# design.net
KiCad netlist of a schematic drawn in Altium Designer
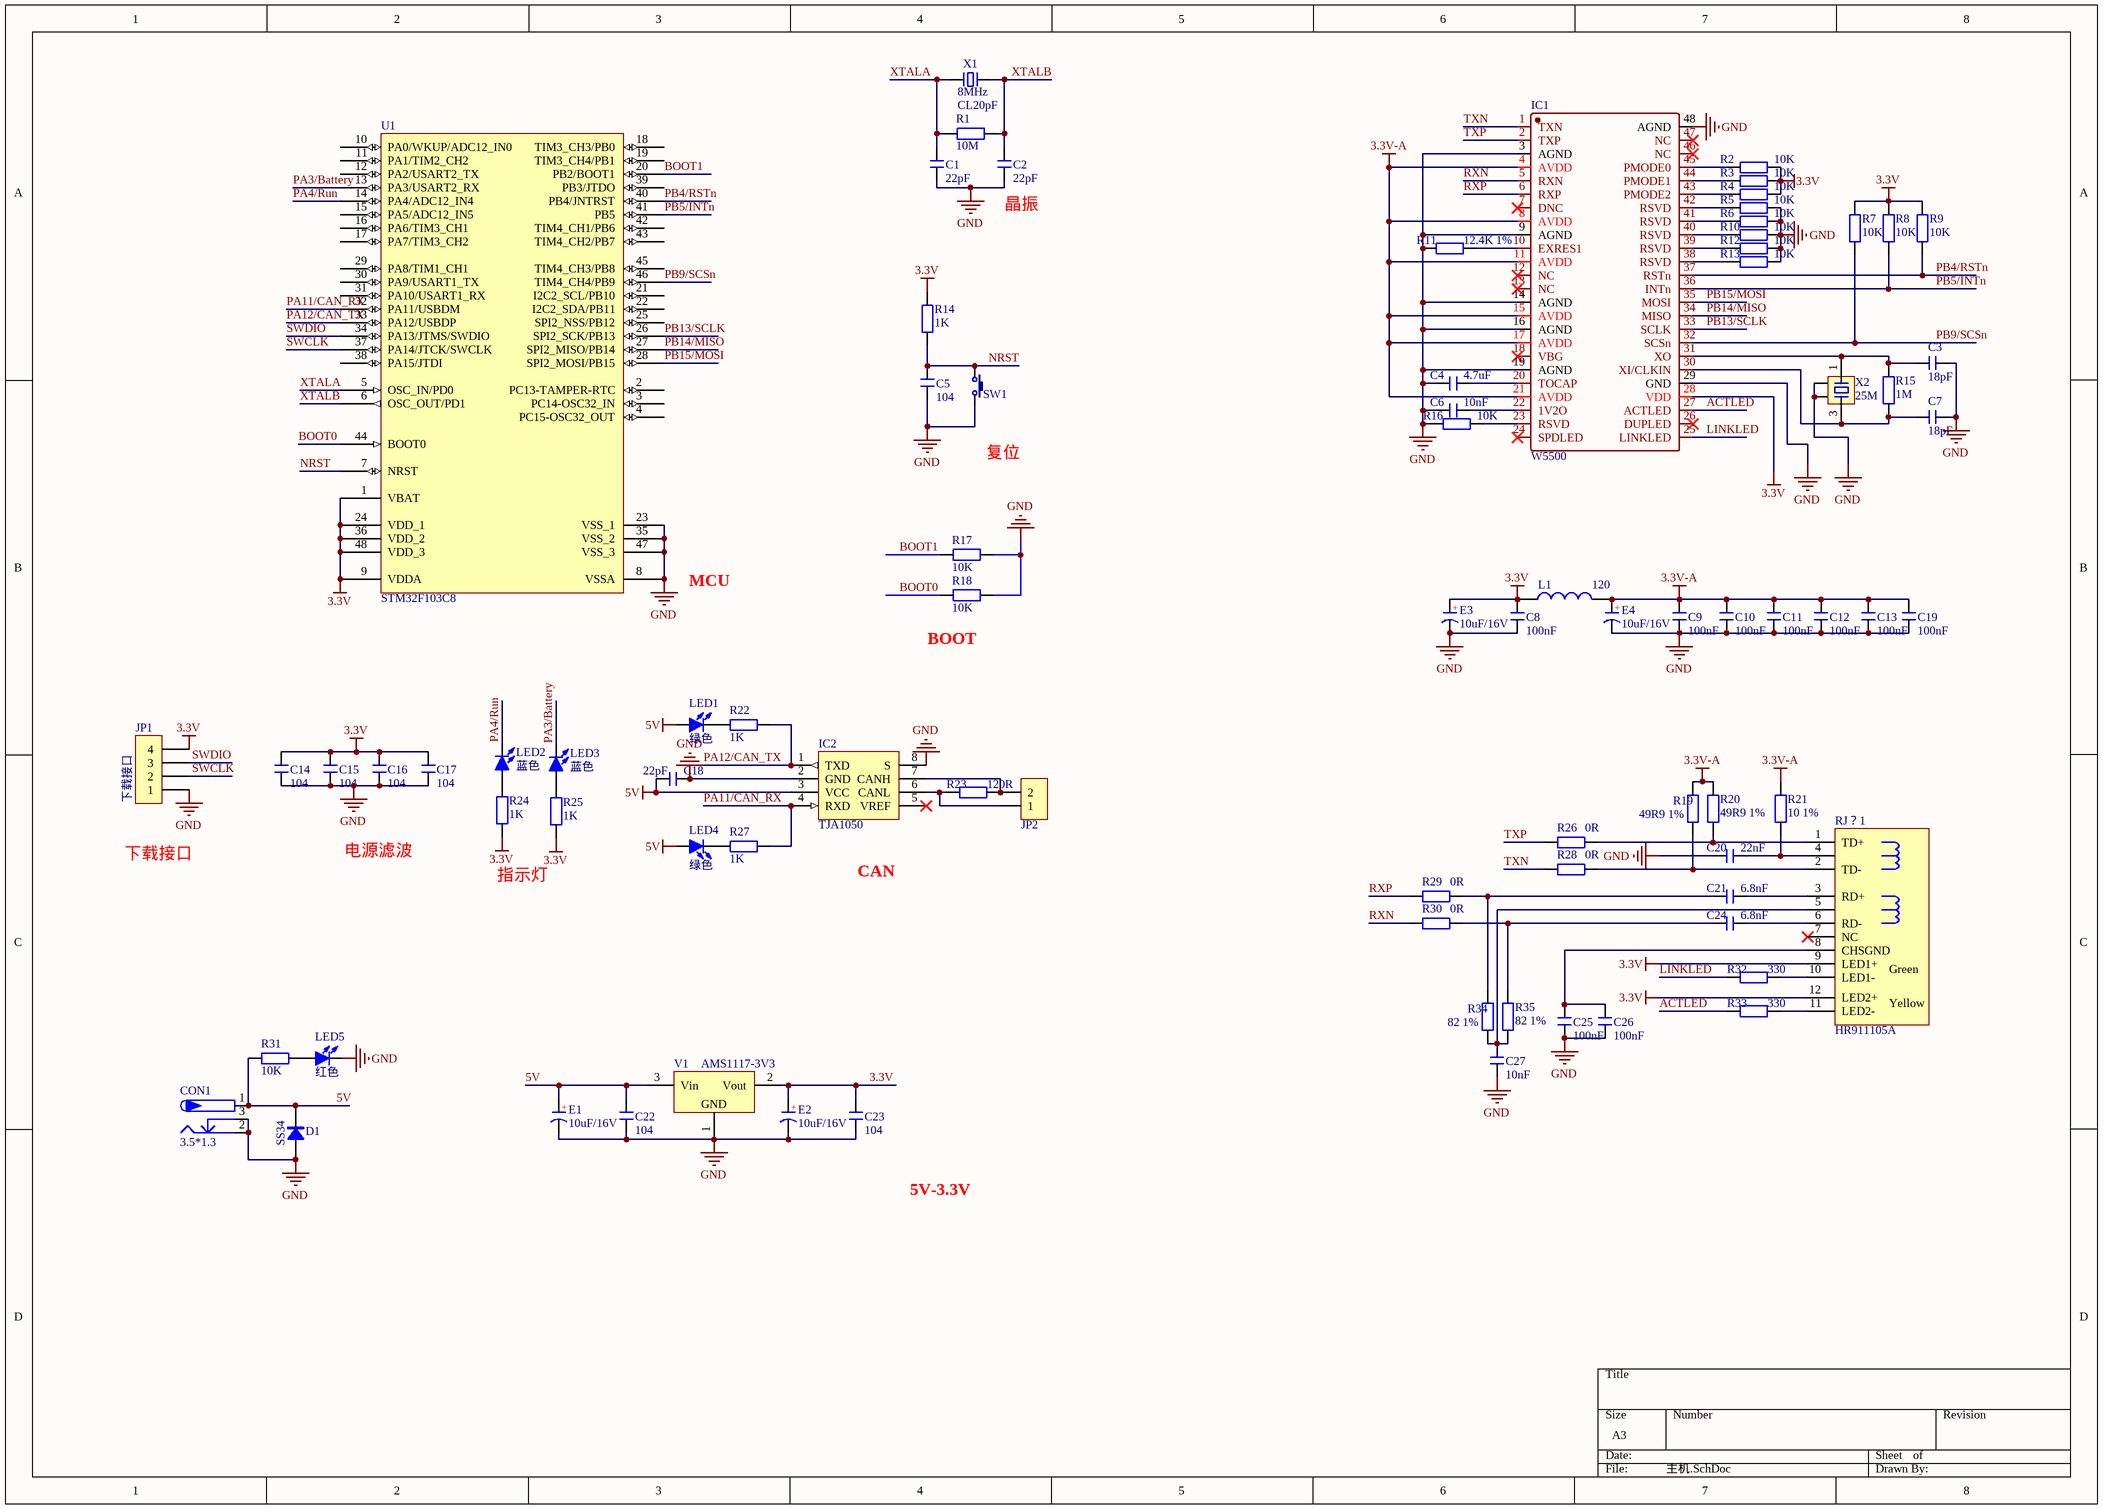
[diagram p0: 主机.SchDoc]

(export (version "E")
  (design (tool "Eeschema 10.0.6"))
  (components
    (comp (ref "C1")
      (value "22pF")
      (footprint "C 0402_L")
      (description "贴片电容")
      (libsource (lib "0.1 - 电阻-电容-电感") (part "C"))
    )
    (comp (ref "C2")
      (value "22pF")
      (footprint "C 0402_L")
      (description "贴片电容")
      (libsource (lib "0.1 - 电阻-电容-电感") (part "C"))
    )
    (comp (ref "C3")
      (value "18pF")
      (footprint "C 0402_L")
      (description "贴片电容")
      (libsource (lib "0.1 - 电阻-电容-电感") (part "C"))
    )
    (comp (ref "C4")
      (value "4.7uF")
      (footprint "C 0402_L")
      (description "贴片电容")
      (libsource (lib "0.1 - 电阻-电容-电感") (part "C"))
    )
    (comp (ref "C5")
      (value "104")
      (footprint "C 0603_L")
      (description "贴片电容")
      (libsource (lib "0.1 - 电阻-电容-电感") (part "C"))
    )
    (comp (ref "C6")
      (value "10nF")
      (footprint "C 0402_L")
      (description "贴片电容")
      (libsource (lib "0.1 - 电阻-电容-电感") (part "C"))
    )
    (comp (ref "C7")
      (value "18pF")
      (footprint "C 0402_L")
      (description "贴片电容")
      (libsource (lib "0.1 - 电阻-电容-电感") (part "C"))
    )
    (comp (ref "C8")
      (value "100nF")
      (footprint "C 0402_L")
      (description "贴片电容")
      (libsource (lib "0.1 - 电阻-电容-电感") (part "C"))
    )
    (comp (ref "C9")
      (value "100nF")
      (footprint "C 0402_L")
      (description "贴片电容")
      (libsource (lib "0.1 - 电阻-电容-电感") (part "C"))
    )
    (comp (ref "C10")
      (value "100nF")
      (footprint "C 0402_L")
      (description "贴片电容")
      (libsource (lib "0.1 - 电阻-电容-电感") (part "C"))
    )
    (comp (ref "C11")
      (value "100nF")
      (footprint "C 0402_L")
      (description "贴片电容")
      (libsource (lib "0.1 - 电阻-电容-电感") (part "C"))
    )
    (comp (ref "C12")
      (value "100nF")
      (footprint "C 0402_L")
      (description "贴片电容")
      (libsource (lib "0.1 - 电阻-电容-电感") (part "C"))
    )
    (comp (ref "C13")
      (value "100nF")
      (footprint "C 0402_L")
      (description "贴片电容")
      (libsource (lib "0.1 - 电阻-电容-电感") (part "C"))
    )
    (comp (ref "C14")
      (value "104")
      (footprint "C 0402_L")
      (description "贴片电容")
      (libsource (lib "0.1 - 电阻-电容-电感") (part "C"))
    )
    (comp (ref "C15")
      (value "104")
      (footprint "C 0402_L")
      (description "贴片电容")
      (libsource (lib "0.1 - 电阻-电容-电感") (part "C"))
    )
    (comp (ref "C16")
      (value "104")
      (footprint "C 0402_L")
      (description "贴片电容")
      (libsource (lib "0.1 - 电阻-电容-电感") (part "C"))
    )
    (comp (ref "C17")
      (value "104")
      (footprint "C 0402_L")
      (description "贴片电容")
      (libsource (lib "0.1 - 电阻-电容-电感") (part "C"))
    )
    (comp (ref "C18")
      (value "22pF")
      (footprint "C 0402_L")
      (description "贴片电容")
      (libsource (lib "0.1 - 电阻-电容-电感") (part "C"))
    )
    (comp (ref "C19")
      (value "100nF")
      (footprint "C 0402_L")
      (description "贴片电容")
      (libsource (lib "0.1 - 电阻-电容-电感") (part "C"))
    )
    (comp (ref "C20")
      (value "22nF")
      (footprint "C 0402_L")
      (description "贴片电容")
      (libsource (lib "0.1 - 电阻-电容-电感") (part "C"))
    )
    (comp (ref "C21")
      (value "6.8nF")
      (footprint "C 0402_L")
      (description "贴片电容")
      (libsource (lib "0.1 - 电阻-电容-电感") (part "C"))
    )
    (comp (ref "C22")
      (value "104")
      (footprint "C 0402_L")
      (description "贴片电容")
      (libsource (lib "0.1 - 电阻-电容-电感") (part "C"))
    )
    (comp (ref "C23")
      (value "104")
      (footprint "C 0402_L")
      (description "贴片电容")
      (libsource (lib "0.1 - 电阻-电容-电感") (part "C"))
    )
    (comp (ref "C24")
      (value "6.8nF")
      (footprint "C 0402_L")
      (description "贴片电容")
      (libsource (lib "0.1 - 电阻-电容-电感") (part "C"))
    )
    (comp (ref "C25")
      (value "100nF")
      (footprint "C 0402_L")
      (description "贴片电容")
      (libsource (lib "0.1 - 电阻-电容-电感") (part "C"))
    )
    (comp (ref "C26")
      (value "100nF")
      (footprint "C 0402_L")
      (description "贴片电容")
      (libsource (lib "0.1 - 电阻-电容-电感") (part "C"))
    )
    (comp (ref "C27")
      (value "10nF")
      (footprint "C 0402_L")
      (description "贴片电容")
      (libsource (lib "0.1 - 电阻-电容-电感") (part "C"))
    )
    (comp (ref "CON1")
      (value "3.5*1.3")
      (footprint "DC-005")
      (description "低压电源接口")
      (fields (field (name "版权归属") "源创客"))
      (libsource (lib "接口类") (part "P-DC"))
    )
    (comp (ref "D1")
      (value "SS34")
      (footprint "SMA")
      (description "肖特基二极管")
      (fields (field (name "版权归属") "源创客"))
      (libsource (lib "二极管-整流桥") (part "SS54"))
    )
    (comp (ref "E1")
      (value "10uF/16V")
      (footprint "CD A(3216)")
      (description "贴片钽电容")
      (libsource (lib "0.1 - 电阻-电容-电感") (part "CT"))
    )
    (comp (ref "E2")
      (value "10uF/16V")
      (footprint "CD A(3216)")
      (description "贴片钽电容")
      (libsource (lib "0.1 - 电阻-电容-电感") (part "CT"))
    )
    (comp (ref "E3")
      (value "10uF/16V")
      (footprint "CD A(3216)")
      (description "贴片钽电容")
      (libsource (lib "0.1 - 电阻-电容-电感") (part "CT"))
    )
    (comp (ref "E4")
      (value "10uF/16V")
      (footprint "CD A(3216)")
      (description "贴片钽电容")
      (libsource (lib "0.1 - 电阻-电容-电感") (part "CT"))
    )
    (comp (ref "IC1")
      (value "W5500")
      (footprint "LQFP48-7*7")
      (description "网口芯片")
      (libsource (lib "1.0 - 常见芯片") (part "W5500"))
    )
    (comp (ref "IC2")
      (value "TJA1050")
      (footprint "SOP8_L")
      (description "CAN总线收发芯片")
      (fields (field (name "版权归属") "封装库来自淘宝 ID：黄晶宝石"))
      (libsource (lib "1.0 - 常见芯片") (part "TJA1050"))
    )
    (comp (ref "JP1")
      (value "下载接口")
      (footprint "下载接口")
      (description "Jlink下载接口")
      (libsource (lib "金手指") (part "下载接口"))
    )
    (comp (ref "JP2")
      (value "HDR-1X2")
      (footprint "KF350-2P")
      (description "2P接插件")
      (fields (field (name "版权归属") "封装库来自淘宝卖家 ID：黄晶宝石"))
      (libsource (lib "5.4 - 接插件-脚距3.5") (part "Header 2"))
    )
    (comp (ref "L1")
      (value "120")
      (footprint "L 0402")
      (description "小功率贴片电感")
      (libsource (lib "0.1 - 电阻-电容-电感") (part "L"))
    )
    (comp (ref "LED1")
      (value "绿色")
      (footprint "LED 0603G")
      (description "贴片LED")
      (fields (field (name "版权归属") "封装库来自淘宝 ID：黄晶宝石"))
      (libsource (lib "0.3 - LED发光二极管") (part "LED-SMD"))
    )
    (comp (ref "LED2")
      (value "蓝色")
      (footprint "LED 0603B")
      (description "贴片LED")
      (fields (field (name "版权归属") "封装库来自淘宝 ID：黄晶宝石"))
      (libsource (lib "0.3 - LED发光二极管") (part "LED-SMD"))
    )
    (comp (ref "LED3")
      (value "蓝色")
      (footprint "LED 0603B")
      (description "贴片LED")
      (fields (field (name "版权归属") "封装库来自淘宝 ID：黄晶宝石"))
      (libsource (lib "0.3 - LED发光二极管") (part "LED-SMD"))
    )
    (comp (ref "LED4")
      (value "绿色")
      (footprint "LED 0603G")
      (description "贴片LED")
      (fields (field (name "版权归属") "封装库来自淘宝 ID：黄晶宝石"))
      (libsource (lib "0.3 - LED发光二极管") (part "LED-SMD"))
    )
    (comp (ref "LED5")
      (value "红色")
      (footprint "LED 0603R")
      (description "贴片LED")
      (fields (field (name "版权归属") "封装库来自淘宝 ID：黄晶宝石"))
      (libsource (lib "0.3 - LED发光二极管") (part "LED-SMD"))
    )
    (comp (ref "R1")
      (value "10M")
      (footprint "R 0402_L")
      (description "贴片电阻")
      (fields (field (name "版权归属") "来自淘宝 ID：黄晶宝石"))
      (libsource (lib "0.1 - 电阻-电容-电感") (part "R"))
    )
    (comp (ref "R2")
      (value "10K")
      (footprint "R 0402_L")
      (description "贴片电阻")
      (fields (field (name "版权归属") "来自淘宝 ID：黄晶宝石"))
      (libsource (lib "0.1 - 电阻-电容-电感") (part "R"))
    )
    (comp (ref "R3")
      (value "10K")
      (footprint "R 0402_L")
      (description "贴片电阻")
      (fields (field (name "版权归属") "来自淘宝 ID：黄晶宝石"))
      (libsource (lib "0.1 - 电阻-电容-电感") (part "R"))
    )
    (comp (ref "R4")
      (value "10K")
      (footprint "R 0402_L")
      (description "贴片电阻")
      (fields (field (name "版权归属") "来自淘宝 ID：黄晶宝石"))
      (libsource (lib "0.1 - 电阻-电容-电感") (part "R"))
    )
    (comp (ref "R5")
      (value "10K")
      (footprint "R 0402_L")
      (description "贴片电阻")
      (fields (field (name "版权归属") "来自淘宝 ID：黄晶宝石"))
      (libsource (lib "0.1 - 电阻-电容-电感") (part "R"))
    )
    (comp (ref "R6")
      (value "10K")
      (footprint "R 0402_L")
      (description "贴片电阻")
      (fields (field (name "版权归属") "来自淘宝 ID：黄晶宝石"))
      (libsource (lib "0.1 - 电阻-电容-电感") (part "R"))
    )
    (comp (ref "R7")
      (value "10K")
      (footprint "R 0402_L")
      (description "贴片电阻")
      (fields (field (name "版权归属") "来自淘宝 ID：黄晶宝石"))
      (libsource (lib "0.1 - 电阻-电容-电感") (part "R"))
    )
    (comp (ref "R8")
      (value "10K")
      (footprint "R 0402_L")
      (description "贴片电阻")
      (fields (field (name "版权归属") "来自淘宝 ID：黄晶宝石"))
      (libsource (lib "0.1 - 电阻-电容-电感") (part "R"))
    )
    (comp (ref "R9")
      (value "10K")
      (footprint "R 0402_L")
      (description "贴片电阻")
      (fields (field (name "版权归属") "来自淘宝 ID：黄晶宝石"))
      (libsource (lib "0.1 - 电阻-电容-电感") (part "R"))
    )
    (comp (ref "R10")
      (value "10K")
      (footprint "R 0402_L")
      (description "贴片电阻")
      (fields (field (name "版权归属") "来自淘宝 ID：黄晶宝石"))
      (libsource (lib "0.1 - 电阻-电容-电感") (part "R"))
    )
    (comp (ref "R11")
      (value "12.4K 1%")
      (footprint "R 0402_L")
      (description "贴片电阻")
      (fields (field (name "版权归属") "来自淘宝 ID：黄晶宝石"))
      (libsource (lib "0.1 - 电阻-电容-电感") (part "R"))
    )
    (comp (ref "R12")
      (value "10K")
      (footprint "R 0402_L")
      (description "贴片电阻")
      (fields (field (name "版权归属") "来自淘宝 ID：黄晶宝石"))
      (libsource (lib "0.1 - 电阻-电容-电感") (part "R"))
    )
    (comp (ref "R13")
      (value "10K")
      (footprint "R 0402_L")
      (description "贴片电阻")
      (fields (field (name "版权归属") "来自淘宝 ID：黄晶宝石"))
      (libsource (lib "0.1 - 电阻-电容-电感") (part "R"))
    )
    (comp (ref "R14")
      (value "1K")
      (footprint "R 0402_L")
      (description "贴片电阻")
      (fields (field (name "版权归属") "来自淘宝 ID：黄晶宝石"))
      (libsource (lib "0.1 - 电阻-电容-电感") (part "R"))
    )
    (comp (ref "R15")
      (value "1M")
      (footprint "R 0402_L")
      (description "贴片电阻")
      (fields (field (name "版权归属") "来自淘宝 ID：黄晶宝石"))
      (libsource (lib "0.1 - 电阻-电容-电感") (part "R"))
    )
    (comp (ref "R16")
      (value "10K")
      (footprint "R 0402_L")
      (description "贴片电阻")
      (fields (field (name "版权归属") "来自淘宝 ID：黄晶宝石"))
      (libsource (lib "0.1 - 电阻-电容-电感") (part "R"))
    )
    (comp (ref "R17")
      (value "10K")
      (footprint "R 0603_L")
      (description "贴片电阻")
      (fields (field (name "版权归属") "来自淘宝 ID：黄晶宝石"))
      (libsource (lib "0.1 - 电阻-电容-电感") (part "R"))
    )
    (comp (ref "R18")
      (value "10K")
      (footprint "R 0603_L")
      (description "贴片电阻")
      (fields (field (name "版权归属") "来自淘宝 ID：黄晶宝石"))
      (libsource (lib "0.1 - 电阻-电容-电感") (part "R"))
    )
    (comp (ref "R19")
      (value "49R9 1%")
      (footprint "R 0402_L")
      (description "贴片电阻")
      (fields (field (name "版权归属") "来自淘宝 ID：黄晶宝石"))
      (libsource (lib "0.1 - 电阻-电容-电感") (part "R"))
    )
    (comp (ref "R20")
      (value "49R9 1%")
      (footprint "R 0402_L")
      (description "贴片电阻")
      (fields (field (name "版权归属") "来自淘宝 ID：黄晶宝石"))
      (libsource (lib "0.1 - 电阻-电容-电感") (part "R"))
    )
    (comp (ref "R21")
      (value "10 1%")
      (footprint "R 0402_L")
      (description "贴片电阻")
      (fields (field (name "版权归属") "来自淘宝 ID：黄晶宝石"))
      (libsource (lib "0.1 - 电阻-电容-电感") (part "R"))
    )
    (comp (ref "R22")
      (value "1K")
      (footprint "R 0402_L")
      (description "贴片电阻")
      (fields (field (name "版权归属") "来自淘宝 ID：黄晶宝石"))
      (libsource (lib "0.1 - 电阻-电容-电感") (part "R"))
    )
    (comp (ref "R23")
      (value "120R")
      (footprint "R 0402_L")
      (description "贴片电阻")
      (fields (field (name "版权归属") "来自淘宝 ID：黄晶宝石"))
      (libsource (lib "0.1 - 电阻-电容-电感") (part "R"))
    )
    (comp (ref "R24")
      (value "1K")
      (footprint "R 0402_L")
      (description "贴片电阻")
      (fields (field (name "版权归属") "来自淘宝 ID：黄晶宝石"))
      (libsource (lib "0.1 - 电阻-电容-电感") (part "R"))
    )
    (comp (ref "R25")
      (value "1K")
      (footprint "R 0402_L")
      (description "贴片电阻")
      (fields (field (name "版权归属") "来自淘宝 ID：黄晶宝石"))
      (libsource (lib "0.1 - 电阻-电容-电感") (part "R"))
    )
    (comp (ref "R26")
      (value "0R")
      (footprint "R 0402_L")
      (description "贴片电阻")
      (fields (field (name "版权归属") "来自淘宝 ID：黄晶宝石"))
      (libsource (lib "0.1 - 电阻-电容-电感") (part "R"))
    )
    (comp (ref "R27")
      (value "1K")
      (footprint "R 0402_L")
      (description "贴片电阻")
      (fields (field (name "版权归属") "来自淘宝 ID：黄晶宝石"))
      (libsource (lib "0.1 - 电阻-电容-电感") (part "R"))
    )
    (comp (ref "R28")
      (value "0R")
      (footprint "R 0402_L")
      (description "贴片电阻")
      (fields (field (name "版权归属") "来自淘宝 ID：黄晶宝石"))
      (libsource (lib "0.1 - 电阻-电容-电感") (part "R"))
    )
    (comp (ref "R29")
      (value "0R")
      (footprint "R 0402_L")
      (description "贴片电阻")
      (fields (field (name "版权归属") "来自淘宝 ID：黄晶宝石"))
      (libsource (lib "0.1 - 电阻-电容-电感") (part "R"))
    )
    (comp (ref "R30")
      (value "0R")
      (footprint "R 0402_L")
      (description "贴片电阻")
      (fields (field (name "版权归属") "来自淘宝 ID：黄晶宝石"))
      (libsource (lib "0.1 - 电阻-电容-电感") (part "R"))
    )
    (comp (ref "R31")
      (value "10K")
      (footprint "R 0402_L")
      (description "贴片电阻")
      (fields (field (name "版权归属") "来自淘宝 ID：黄晶宝石"))
      (libsource (lib "0.1 - 电阻-电容-电感") (part "R"))
    )
    (comp (ref "R32")
      (value "330")
      (footprint "R 0402_L")
      (description "贴片电阻")
      (fields (field (name "版权归属") "来自淘宝 ID：黄晶宝石"))
      (libsource (lib "0.1 - 电阻-电容-电感") (part "R"))
    )
    (comp (ref "R33")
      (value "330")
      (footprint "R 0402_L")
      (description "贴片电阻")
      (fields (field (name "版权归属") "来自淘宝 ID：黄晶宝石"))
      (libsource (lib "0.1 - 电阻-电容-电感") (part "R"))
    )
    (comp (ref "R34")
      (value "82 1%")
      (footprint "R 0402_L")
      (description "贴片电阻")
      (fields (field (name "版权归属") "来自淘宝 ID：黄晶宝石"))
      (libsource (lib "0.1 - 电阻-电容-电感") (part "R"))
    )
    (comp (ref "R35")
      (value "82 1%")
      (footprint "R 0402_L")
      (description "贴片电阻")
      (fields (field (name "版权归属") "来自淘宝 ID：黄晶宝石"))
      (libsource (lib "0.1 - 电阻-电容-电感") (part "R"))
    )
    (comp (ref "RJ？1")
      (value "HR911105A")
      (footprint "RJ-45A12")
      (description "带灯以太网接口")
      (fields (field (name "版权归属") "封装库来自淘宝 ID：黄晶宝石"))
      (libsource (lib "0.8 - 以太网-音频-USB插座") (part "HR911105A"))
    )
    (comp (ref "SW1")
      (value "3x6x5")
      (footprint "TSW SMD-3*6*2.5")
      (description "3x6轻触开关")
      (fields (field (name "版权归属") "源创客"))
      (libsource (lib "按键-开关") (part "TSW 3x6"))
    )
    (comp (ref "U1")
      (value "STM32F103C8")
      (footprint "LQFP48 7X7_L")
      (description "Flaah:64/RAM:20/IO:36")
      (fields (field (name "版权归属") "源创客"))
      (libsource (lib "STM32系列单片机") (part "STM32F103C8"))
    )
    (comp (ref "V1")
      (value "AMS1117-3V3")
      (footprint "SOT223_L")
      (description "三端稳压芯片")
      (libsource (lib "1.1 - 电源类芯片") (part "AMS1117"))
    )
    (comp (ref "X1")
      (value "8MHz")
      (footprint "OSC 5032-2P")
      (description "2脚无源脚晶振")
      (fields (field (name "负载电容") "CL20pF") (field (name "版权归属") "源创客"))
      (libsource (lib "保险丝-晶振") (part "XTAL-2P"))
    )
    (comp (ref "X2")
      (value "25M")
      (footprint "OSC 3225-4P")
      (description "4脚无源晶振")
      (fields (field (name "版权归属") "封装库来自淘宝卖家 ID：黄晶宝石"))
      (libsource (lib "2.0 - 保险丝-晶振-光耦") (part "XTAL-4P"))
    )
  )
  (nets
    (net (code "2") (name "/ACTLED") (class "Default")
      (node (ref "IC1") (pin "27") (pinfunction "ACTLED_27") (pintype "passive"))
      (node (ref "R33") (pin "2") (pinfunction "2_2") (pintype "passive"))
    )
    (net (code "3") (name "/BOOT0") (class "Default")
      (node (ref "R18") (pin "1") (pinfunction "1_1") (pintype "passive"))
      (node (ref "U1") (pin "44") (pinfunction "BOOT0_44") (pintype "input"))
    )
    (net (code "4") (name "/BOOT1") (class "Default")
      (node (ref "R17") (pin "1") (pinfunction "1_1") (pintype "passive"))
      (node (ref "U1") (pin "20") (pinfunction "PB2/BOOT1_20") (pintype "bidirectional"))
    )
    (net (code "5") (name "/LINKLED") (class "Default")
      (node (ref "IC1") (pin "25") (pinfunction "LINKLED_25") (pintype "passive"))
      (node (ref "R32") (pin "2") (pinfunction "2_2") (pintype "passive"))
    )
    (net (code "6") (name "/NRST") (class "Default")
      (node (ref "C5") (pin "2") (pinfunction "2_2") (pintype "passive"))
      (node (ref "R14") (pin "1") (pinfunction "1_1") (pintype "passive"))
      (node (ref "SW1") (pin "1") (pinfunction "1_1") (pintype "passive"))
      (node (ref "U1") (pin "7") (pinfunction "NRST_7") (pintype "bidirectional"))
    )
    (net (code "7") (name "/PA3{slash}Battery") (class "Default")
      (node (ref "LED3") (pin "2") (pinfunction "K_2") (pintype "passive"))
      (node (ref "U1") (pin "13") (pinfunction "PA3/USART2_RX_13") (pintype "bidirectional"))
    )
    (net (code "8") (name "/PA4{slash}Run") (class "Default")
      (node (ref "LED2") (pin "2") (pinfunction "K_2") (pintype "passive"))
      (node (ref "U1") (pin "14") (pinfunction "PA4/ADC12_IN4_14") (pintype "bidirectional"))
    )
    (net (code "9") (name "/PA11{slash}CAN_RX") (class "Default")
      (node (ref "IC2") (pin "4") (pinfunction "RXD_4") (pintype "input"))
      (node (ref "R27") (pin "1") (pinfunction "1_1") (pintype "passive"))
      (node (ref "U1") (pin "32") (pinfunction "PA11/USBDM_32") (pintype "bidirectional"))
    )
    (net (code "10") (name "/PA12{slash}CAN_TX") (class "Default")
      (node (ref "IC2") (pin "1") (pinfunction "TXD_1") (pintype "output"))
      (node (ref "R22") (pin "1") (pinfunction "1_1") (pintype "passive"))
      (node (ref "U1") (pin "33") (pinfunction "PA12/USBDP_33") (pintype "bidirectional"))
    )
    (net (code "11") (name "/PB4{slash}RSTn") (class "Default")
      (node (ref "IC1") (pin "37") (pinfunction "RSTn_37") (pintype "passive"))
      (node (ref "R9") (pin "1") (pinfunction "1_1") (pintype "passive"))
      (node (ref "U1") (pin "40") (pinfunction "PB4/JNTRST_40") (pintype "bidirectional"))
    )
    (net (code "12") (name "/PB5{slash}INTn") (class "Default")
      (node (ref "IC1") (pin "36") (pinfunction "INTn_36") (pintype "passive"))
      (node (ref "R8") (pin "1") (pinfunction "1_1") (pintype "passive"))
      (node (ref "U1") (pin "41") (pinfunction "PB5_41") (pintype "bidirectional"))
    )
    (net (code "13") (name "/PB9{slash}SCSn") (class "Default")
      (node (ref "IC1") (pin "32") (pinfunction "SCSn_32") (pintype "passive"))
      (node (ref "R7") (pin "1") (pinfunction "1_1") (pintype "passive"))
      (node (ref "U1") (pin "46") (pinfunction "TIM4_CH4/PB9_46") (pintype "bidirectional"))
    )
    (net (code "14") (name "/PB13{slash}SCLK") (class "Default")
      (node (ref "IC1") (pin "33") (pinfunction "SCLK_33") (pintype "passive"))
      (node (ref "U1") (pin "26") (pinfunction "SPI2_SCK/PB13_26") (pintype "bidirectional"))
    )
    (net (code "15") (name "/PB14{slash}MISO") (class "Default")
      (node (ref "IC1") (pin "34") (pinfunction "MISO_34") (pintype "passive"))
      (node (ref "U1") (pin "27") (pinfunction "SPI2_MISO/PB14_27") (pintype "bidirectional"))
    )
    (net (code "16") (name "/PB15{slash}MOSI") (class "Default")
      (node (ref "IC1") (pin "35") (pinfunction "MOSI_35") (pintype "passive"))
      (node (ref "U1") (pin "28") (pinfunction "SPI2_MOSI/PB15_28") (pintype "bidirectional"))
    )
    (net (code "17") (name "/RXN") (class "Default")
      (node (ref "IC1") (pin "5") (pinfunction "RXN_5") (pintype "passive"))
      (node (ref "R30") (pin "2") (pinfunction "2_2") (pintype "passive"))
    )
    (net (code "18") (name "/RXP") (class "Default")
      (node (ref "IC1") (pin "6") (pinfunction "RXP_6") (pintype "passive"))
      (node (ref "R29") (pin "2") (pinfunction "2_2") (pintype "passive"))
    )
    (net (code "19") (name "/SWCLK") (class "Default")
      (node (ref "JP1") (pin "2") (pinfunction "2_2") (pintype "passive"))
      (node (ref "U1") (pin "37") (pinfunction "PA14/JTCK/SWCLK_37") (pintype "bidirectional"))
    )
    (net (code "20") (name "/SWDIO") (class "Default")
      (node (ref "JP1") (pin "3") (pinfunction "3_3") (pintype "passive"))
      (node (ref "U1") (pin "34") (pinfunction "PA13/JTMS/SWDIO_34") (pintype "bidirectional"))
    )
    (net (code "21") (name "/TXN") (class "Default")
      (node (ref "IC1") (pin "1") (pinfunction "TXN_1") (pintype "passive"))
      (node (ref "R28") (pin "2") (pinfunction "2_2") (pintype "passive"))
    )
    (net (code "22") (name "/TXP") (class "Default")
      (node (ref "IC1") (pin "2") (pinfunction "TXP_2") (pintype "passive"))
      (node (ref "R26") (pin "2") (pinfunction "2_2") (pintype "passive"))
    )
    (net (code "23") (name "/XTALA") (class "Default")
      (node (ref "C1") (pin "2") (pinfunction "2_2") (pintype "passive"))
      (node (ref "R1") (pin "1") (pinfunction "1_1") (pintype "passive"))
      (node (ref "U1") (pin "5") (pinfunction "OSC_IN/PD0_5") (pintype "input"))
      (node (ref "X1") (pin "1") (pinfunction "1_1") (pintype "passive"))
    )
    (net (code "24") (name "/XTALB") (class "Default")
      (node (ref "C2") (pin "2") (pinfunction "2_2") (pintype "passive"))
      (node (ref "R1") (pin "2") (pinfunction "2_2") (pintype "passive"))
      (node (ref "U1") (pin "6") (pinfunction "OSC_OUT/PD1_6") (pintype "output"))
      (node (ref "X1") (pin "2") (pinfunction "2_2") (pintype "passive"))
    )
    (net (code "25") (name "3.3V") (class "Default")
      (node (ref "C14") (pin "2") (pinfunction "2_2") (pintype "passive"))
      (node (ref "C15") (pin "2") (pinfunction "2_2") (pintype "passive"))
      (node (ref "C16") (pin "2") (pinfunction "2_2") (pintype "passive"))
      (node (ref "C17") (pin "2") (pinfunction "2_2") (pintype "passive"))
      (node (ref "C23") (pin "2") (pinfunction "2_2") (pintype "passive"))
      (node (ref "C8") (pin "2") (pinfunction "2_2") (pintype "passive"))
      (node (ref "E2") (pin "1") (pinfunction "A_1") (pintype "passive"))
      (node (ref "E3") (pin "1") (pinfunction "A_1") (pintype "passive"))
      (node (ref "IC1") (pin "28") (pinfunction "VDD_28") (pintype "passive"))
      (node (ref "JP1") (pin "4") (pinfunction "4_4") (pintype "passive"))
      (node (ref "L1") (pin "1") (pinfunction "1_1") (pintype "passive"))
      (node (ref "R14") (pin "2") (pinfunction "2_2") (pintype "passive"))
      (node (ref "R2") (pin "2") (pinfunction "2_2") (pintype "passive"))
      (node (ref "R24") (pin "2") (pinfunction "2_2") (pintype "passive"))
      (node (ref "R25") (pin "2") (pinfunction "2_2") (pintype "passive"))
      (node (ref "R3") (pin "2") (pinfunction "2_2") (pintype "passive"))
      (node (ref "R4") (pin "2") (pinfunction "2_2") (pintype "passive"))
      (node (ref "R7") (pin "2") (pinfunction "2_2") (pintype "passive"))
      (node (ref "R8") (pin "2") (pinfunction "2_2") (pintype "passive"))
      (node (ref "R9") (pin "2") (pinfunction "2_2") (pintype "passive"))
      (node (ref "RJ？1") (pin "12") (pinfunction "LED2+_12") (pintype "passive"))
      (node (ref "RJ？1") (pin "9") (pinfunction "LED1+_9") (pintype "passive"))
      (node (ref "U1") (pin "1") (pinfunction "VBAT_1") (pintype "power_in"))
      (node (ref "U1") (pin "24") (pinfunction "VDD_1_24") (pintype "power_in"))
      (node (ref "U1") (pin "36") (pinfunction "VDD_2_36") (pintype "power_in"))
      (node (ref "U1") (pin "48") (pinfunction "VDD_3_48") (pintype "power_in"))
      (node (ref "U1") (pin "9") (pinfunction "VDDA_9") (pintype "power_in"))
      (node (ref "V1") (pin "2") (pinfunction "Vout_2") (pintype "passive"))
    )
    (net (code "26") (name "3.3V-A") (class "Default")
      (node (ref "C10") (pin "1") (pinfunction "1_1") (pintype "passive"))
      (node (ref "C11") (pin "1") (pinfunction "1_1") (pintype "passive"))
      (node (ref "C12") (pin "1") (pinfunction "1_1") (pintype "passive"))
      (node (ref "C13") (pin "1") (pinfunction "1_1") (pintype "passive"))
      (node (ref "C19") (pin "1") (pinfunction "1_1") (pintype "passive"))
      (node (ref "C9") (pin "1") (pinfunction "1_1") (pintype "passive"))
      (node (ref "E4") (pin "1") (pinfunction "A_1") (pintype "passive"))
      (node (ref "IC1") (pin "11") (pinfunction "AVDD_11") (pintype "passive"))
      (node (ref "IC1") (pin "15") (pinfunction "AVDD_15") (pintype "passive"))
      (node (ref "IC1") (pin "17") (pinfunction "AVDD_17") (pintype "passive"))
      (node (ref "IC1") (pin "21") (pinfunction "AVDD_21") (pintype "passive"))
      (node (ref "IC1") (pin "4") (pinfunction "AVDD_4") (pintype "passive"))
      (node (ref "IC1") (pin "8") (pinfunction "AVDD_8") (pintype "passive"))
      (node (ref "L1") (pin "2") (pinfunction "2_2") (pintype "passive"))
      (node (ref "R19") (pin "2") (pinfunction "2_2") (pintype "passive"))
      (node (ref "R20") (pin "2") (pinfunction "2_2") (pintype "passive"))
      (node (ref "R21") (pin "2") (pinfunction "2_2") (pintype "passive"))
    )
    (net (code "27") (name "5V") (class "Default")
      (node (ref "C18") (pin "2") (pinfunction "2_2") (pintype "passive"))
      (node (ref "C22") (pin "2") (pinfunction "2_2") (pintype "passive"))
      (node (ref "CON1") (pin "1") (pintype "power_in"))
      (node (ref "D1") (pin "2") (pinfunction "K_2") (pintype "passive"))
      (node (ref "E1") (pin "1") (pinfunction "A_1") (pintype "passive"))
      (node (ref "IC2") (pin "3") (pinfunction "VCC_3") (pintype "passive"))
      (node (ref "LED1") (pin "1") (pinfunction "A_1") (pintype "passive"))
      (node (ref "LED4") (pin "1") (pinfunction "A_1") (pintype "passive"))
      (node (ref "R31") (pin "1") (pinfunction "1_1") (pintype "passive"))
      (node (ref "V1") (pin "3") (pinfunction "Vin_3") (pintype "passive"))
    )
    (net (code "28") (name "GND") (class "Default")
      (node (ref "C1") (pin "1") (pinfunction "1_1") (pintype "passive"))
      (node (ref "C10") (pin "2") (pinfunction "2_2") (pintype "passive"))
      (node (ref "C11") (pin "2") (pinfunction "2_2") (pintype "passive"))
      (node (ref "C12") (pin "2") (pinfunction "2_2") (pintype "passive"))
      (node (ref "C13") (pin "2") (pinfunction "2_2") (pintype "passive"))
      (node (ref "C14") (pin "1") (pinfunction "1_1") (pintype "passive"))
      (node (ref "C15") (pin "1") (pinfunction "1_1") (pintype "passive"))
      (node (ref "C16") (pin "1") (pinfunction "1_1") (pintype "passive"))
      (node (ref "C17") (pin "1") (pinfunction "1_1") (pintype "passive"))
      (node (ref "C18") (pin "1") (pinfunction "1_1") (pintype "passive"))
      (node (ref "C19") (pin "2") (pinfunction "2_2") (pintype "passive"))
      (node (ref "C2") (pin "1") (pinfunction "1_1") (pintype "passive"))
      (node (ref "C20") (pin "2") (pinfunction "2_2") (pintype "passive"))
      (node (ref "C22") (pin "1") (pinfunction "1_1") (pintype "passive"))
      (node (ref "C23") (pin "1") (pinfunction "1_1") (pintype "passive"))
      (node (ref "C25") (pin "1") (pinfunction "1_1") (pintype "passive"))
      (node (ref "C26") (pin "1") (pinfunction "1_1") (pintype "passive"))
      (node (ref "C27") (pin "2") (pinfunction "2_2") (pintype "passive"))
      (node (ref "C3") (pin "1") (pinfunction "1_1") (pintype "passive"))
      (node (ref "C4") (pin "2") (pinfunction "2_2") (pintype "passive"))
      (node (ref "C5") (pin "1") (pinfunction "1_1") (pintype "passive"))
      (node (ref "C6") (pin "2") (pinfunction "2_2") (pintype "passive"))
      (node (ref "C7") (pin "1") (pinfunction "1_1") (pintype "passive"))
      (node (ref "C8") (pin "1") (pinfunction "1_1") (pintype "passive"))
      (node (ref "C9") (pin "2") (pinfunction "2_2") (pintype "passive"))
      (node (ref "CON1") (pin "2") (pintype "power_in"))
      (node (ref "CON1") (pin "3") (pintype "power_in"))
      (node (ref "D1") (pin "1") (pinfunction "A_1") (pintype "passive"))
      (node (ref "E1") (pin "2") (pinfunction "K_2") (pintype "passive"))
      (node (ref "E2") (pin "2") (pinfunction "K_2") (pintype "passive"))
      (node (ref "E3") (pin "2") (pinfunction "K_2") (pintype "passive"))
      (node (ref "E4") (pin "2") (pinfunction "K_2") (pintype "passive"))
      (node (ref "IC1") (pin "14") (pinfunction "AGND_14") (pintype "passive"))
      (node (ref "IC1") (pin "16") (pinfunction "AGND_16") (pintype "passive"))
      (node (ref "IC1") (pin "19") (pinfunction "AGND_19") (pintype "passive"))
      (node (ref "IC1") (pin "29") (pinfunction "GND_29") (pintype "passive"))
      (node (ref "IC1") (pin "3") (pinfunction "AGND_3") (pintype "passive"))
      (node (ref "IC1") (pin "48") (pinfunction "AGND_48") (pintype "passive"))
      (node (ref "IC1") (pin "9") (pinfunction "AGND_9") (pintype "passive"))
      (node (ref "IC2") (pin "2") (pinfunction "GND_2") (pintype "passive"))
      (node (ref "IC2") (pin "8") (pinfunction "S_8") (pintype "passive"))
      (node (ref "JP1") (pin "1") (pinfunction "1_1") (pintype "passive"))
      (node (ref "LED5") (pin "2") (pinfunction "K_2") (pintype "passive"))
      (node (ref "R10") (pin "2") (pinfunction "2_2") (pintype "passive"))
      (node (ref "R11") (pin "1") (pinfunction "1_1") (pintype "passive"))
      (node (ref "R12") (pin "2") (pinfunction "2_2") (pintype "passive"))
      (node (ref "R13") (pin "2") (pinfunction "2_2") (pintype "passive"))
      (node (ref "R16") (pin "1") (pinfunction "1_1") (pintype "passive"))
      (node (ref "R17") (pin "2") (pinfunction "2_2") (pintype "passive"))
      (node (ref "R18") (pin "2") (pinfunction "2_2") (pintype "passive"))
      (node (ref "R5") (pin "2") (pinfunction "2_2") (pintype "passive"))
      (node (ref "R6") (pin "2") (pinfunction "2_2") (pintype "passive"))
      (node (ref "SW1") (pin "2") (pinfunction "2_2") (pintype "passive"))
      (node (ref "U1") (pin "23") (pinfunction "VSS_1_23") (pintype "power_in"))
      (node (ref "U1") (pin "35") (pinfunction "VSS_2_35") (pintype "power_in"))
      (node (ref "U1") (pin "47") (pinfunction "VSS_3_47") (pintype "power_in"))
      (node (ref "U1") (pin "8") (pinfunction "VSSA_8") (pintype "power_in"))
      (node (ref "V1") (pin "1") (pinfunction "GND_1") (pintype "passive"))
      (node (ref "X2") (pin "2") (pinfunction "2_2") (pintype "passive"))
      (node (ref "X2") (pin "4") (pinfunction "4_4") (pintype "passive"))
    )
    (net (code "29") (name "Net-(C20-Pad1)") (class "Default")
      (node (ref "C20") (pin "1") (pinfunction "1_1") (pintype "passive"))
      (node (ref "R21") (pin "1") (pinfunction "1_1") (pintype "passive"))
      (node (ref "RJ？1") (pin "4") (pintype "passive"))
    )
    (net (code "30") (name "Net-(C21-Pad2)") (class "Default")
      (node (ref "C21") (pin "2") (pinfunction "2_2") (pintype "passive"))
      (node (ref "R29") (pin "1") (pinfunction "1_1") (pintype "passive"))
      (node (ref "R34") (pin "2") (pinfunction "2_2") (pintype "passive"))
    )
    (net (code "31") (name "Net-(C24-Pad2)") (class "Default")
      (node (ref "C24") (pin "2") (pinfunction "2_2") (pintype "passive"))
      (node (ref "R30") (pin "1") (pinfunction "1_1") (pintype "passive"))
      (node (ref "R35") (pin "1") (pinfunction "1_1") (pintype "passive"))
    )
    (net (code "32") (name "Net-(C27-Pad1)") (class "Default")
      (node (ref "C27") (pin "1") (pinfunction "1_1") (pintype "passive"))
      (node (ref "R34") (pin "1") (pinfunction "1_1") (pintype "passive"))
      (node (ref "R35") (pin "2") (pinfunction "2_2") (pintype "passive"))
      (node (ref "RJ？1") (pin "5") (pintype "passive"))
    )
    (net (code "33") (name "Net-(IC1-1V2O)") (class "Default")
      (node (ref "C6") (pin "1") (pinfunction "1_1") (pintype "passive"))
      (node (ref "IC1") (pin "22") (pinfunction "1V2O_22") (pintype "passive"))
    )
    (net (code "34") (name "Net-(IC1-EXRES1)") (class "Default")
      (node (ref "IC1") (pin "10") (pinfunction "EXRES1_10") (pintype "passive"))
      (node (ref "R11") (pin "2") (pinfunction "2_2") (pintype "passive"))
    )
    (net (code "35") (name "Net-(IC1-PMODE0)") (class "Default")
      (node (ref "IC1") (pin "45") (pinfunction "PMODE0_45") (pintype "passive"))
      (node (ref "R2") (pin "1") (pinfunction "1_1") (pintype "passive"))
    )
    (net (code "36") (name "Net-(IC1-PMODE1)") (class "Default")
      (node (ref "IC1") (pin "44") (pinfunction "PMODE1_44") (pintype "passive"))
      (node (ref "R3") (pin "1") (pinfunction "1_1") (pintype "passive"))
    )
    (net (code "37") (name "Net-(IC1-PMODE2)") (class "Default")
      (node (ref "IC1") (pin "43") (pinfunction "PMODE2_43") (pintype "passive"))
      (node (ref "R4") (pin "1") (pinfunction "1_1") (pintype "passive"))
    )
    (net (code "38") (name "Net-(IC1-RSVD-Pad23)") (class "Default")
      (node (ref "IC1") (pin "23") (pinfunction "RSVD_23") (pintype "passive"))
      (node (ref "R16") (pin "2") (pinfunction "2_2") (pintype "passive"))
    )
    (net (code "39") (name "Net-(IC1-RSVD-Pad38)") (class "Default")
      (node (ref "IC1") (pin "38") (pinfunction "RSVD_38") (pintype "passive"))
      (node (ref "R13") (pin "1") (pinfunction "1_1") (pintype "passive"))
    )
    (net (code "40") (name "Net-(IC1-RSVD-Pad39)") (class "Default")
      (node (ref "IC1") (pin "39") (pinfunction "RSVD_39") (pintype "passive"))
      (node (ref "R12") (pin "1") (pinfunction "1_1") (pintype "passive"))
    )
    (net (code "41") (name "Net-(IC1-RSVD-Pad40)") (class "Default")
      (node (ref "IC1") (pin "40") (pinfunction "RSVD_40") (pintype "passive"))
      (node (ref "R10") (pin "1") (pinfunction "1_1") (pintype "passive"))
    )
    (net (code "42") (name "Net-(IC1-RSVD-Pad41)") (class "Default")
      (node (ref "IC1") (pin "41") (pinfunction "RSVD_41") (pintype "passive"))
      (node (ref "R6") (pin "1") (pinfunction "1_1") (pintype "passive"))
    )
    (net (code "43") (name "Net-(IC1-RSVD-Pad42)") (class "Default")
      (node (ref "IC1") (pin "42") (pinfunction "RSVD_42") (pintype "passive"))
      (node (ref "R5") (pin "1") (pinfunction "1_1") (pintype "passive"))
    )
    (net (code "44") (name "Net-(IC1-TOCAP)") (class "Default")
      (node (ref "C4") (pin "1") (pinfunction "1_1") (pintype "passive"))
      (node (ref "IC1") (pin "20") (pinfunction "TOCAP_20") (pintype "passive"))
    )
    (net (code "45") (name "Net-(IC1-XI{slash}CLKIN)") (class "Default")
      (node (ref "C7") (pin "2") (pinfunction "2_2") (pintype "passive"))
      (node (ref "IC1") (pin "30") (pinfunction "XI/CLKIN_30") (pintype "passive"))
      (node (ref "R15") (pin "1") (pinfunction "1_1") (pintype "passive"))
      (node (ref "X2") (pin "3") (pinfunction "3_3") (pintype "passive"))
    )
    (net (code "46") (name "Net-(IC1-XO)") (class "Default")
      (node (ref "C3") (pin "2") (pinfunction "2_2") (pintype "passive"))
      (node (ref "IC1") (pin "31") (pinfunction "XO_31") (pintype "passive"))
      (node (ref "R15") (pin "2") (pinfunction "2_2") (pintype "passive"))
      (node (ref "X2") (pin "1") (pinfunction "1_1") (pintype "passive"))
    )
    (net (code "47") (name "Net-(IC2-CANH)") (class "Default")
      (node (ref "IC2") (pin "7") (pinfunction "CANH_7") (pintype "passive"))
      (node (ref "JP2") (pin "2") (pinfunction "2_2") (pintype "passive"))
      (node (ref "R23") (pin "1") (pinfunction "1_1") (pintype "passive"))
    )
    (net (code "48") (name "Net-(IC2-CANL)") (class "Default")
      (node (ref "IC2") (pin "6") (pinfunction "CANL_6") (pintype "passive"))
      (node (ref "JP2") (pin "1") (pinfunction "1_1") (pintype "passive"))
      (node (ref "R23") (pin "2") (pinfunction "2_2") (pintype "passive"))
    )
    (net (code "49") (name "Net-(LED1-K)") (class "Default")
      (node (ref "LED1") (pin "2") (pinfunction "K_2") (pintype "passive"))
      (node (ref "R22") (pin "2") (pinfunction "2_2") (pintype "passive"))
    )
    (net (code "50") (name "Net-(LED2-A)") (class "Default")
      (node (ref "LED2") (pin "1") (pinfunction "A_1") (pintype "passive"))
      (node (ref "R24") (pin "1") (pinfunction "1_1") (pintype "passive"))
    )
    (net (code "51") (name "Net-(LED3-A)") (class "Default")
      (node (ref "LED3") (pin "1") (pinfunction "A_1") (pintype "passive"))
      (node (ref "R25") (pin "1") (pinfunction "1_1") (pintype "passive"))
    )
    (net (code "52") (name "Net-(LED4-K)") (class "Default")
      (node (ref "LED4") (pin "2") (pinfunction "K_2") (pintype "passive"))
      (node (ref "R27") (pin "2") (pinfunction "2_2") (pintype "passive"))
    )
    (net (code "53") (name "Net-(LED5-A)") (class "Default")
      (node (ref "LED5") (pin "1") (pinfunction "A_1") (pintype "passive"))
      (node (ref "R31") (pin "2") (pinfunction "2_2") (pintype "passive"))
    )
    (net (code "54") (name "Net-(RJ？1-CHSGND)") (class "Default")
      (node (ref "C25") (pin "2") (pinfunction "2_2") (pintype "passive"))
      (node (ref "C26") (pin "2") (pinfunction "2_2") (pintype "passive"))
      (node (ref "RJ？1") (pin "8") (pinfunction "CHSGND_8") (pintype "passive"))
    )
    (net (code "55") (name "Net-(RJ？1-LED1-)") (class "Default")
      (node (ref "R32") (pin "1") (pinfunction "1_1") (pintype "passive"))
      (node (ref "RJ？1") (pin "10") (pinfunction "LED1-_10") (pintype "passive"))
    )
    (net (code "56") (name "Net-(RJ？1-LED2-)") (class "Default")
      (node (ref "R33") (pin "1") (pinfunction "1_1") (pintype "passive"))
      (node (ref "RJ？1") (pin "11") (pinfunction "LED2-_11") (pintype "passive"))
    )
    (net (code "57") (name "Net-(RJ？1-RD+)") (class "Default")
      (node (ref "C21") (pin "1") (pinfunction "1_1") (pintype "passive"))
      (node (ref "RJ？1") (pin "3") (pinfunction "RD+_3") (pintype "passive"))
    )
    (net (code "58") (name "Net-(RJ？1-RD-)") (class "Default")
      (node (ref "C24") (pin "1") (pinfunction "1_1") (pintype "passive"))
      (node (ref "RJ？1") (pin "6") (pinfunction "RD-_6") (pintype "passive"))
    )
    (net (code "59") (name "Net-(RJ？1-TD+)") (class "Default")
      (node (ref "R20") (pin "1") (pinfunction "1_1") (pintype "passive"))
      (node (ref "R26") (pin "1") (pinfunction "1_1") (pintype "passive"))
      (node (ref "RJ？1") (pin "1") (pinfunction "TD+_1") (pintype "passive"))
    )
    (net (code "60") (name "Net-(RJ？1-TD-)") (class "Default")
      (node (ref "R19") (pin "1") (pinfunction "1_1") (pintype "passive"))
      (node (ref "R28") (pin "1") (pinfunction "1_1") (pintype "passive"))
      (node (ref "RJ？1") (pin "2") (pinfunction "TD-_2") (pintype "passive"))
    )
    (net (code "61") (name "unconnected-(IC1-DNC-Pad7)") (class "Default")
      (node (ref "IC1") (pin "7") (pinfunction "DNC_7") (pintype "passive+no_connect"))
    )
    (net (code "62") (name "unconnected-(IC1-DUPLED-Pad26)") (class "Default")
      (node (ref "IC1") (pin "26") (pinfunction "DUPLED_26") (pintype "passive+no_connect"))
    )
    (net (code "63") (name "unconnected-(IC1-NC-Pad12)") (class "Default")
      (node (ref "IC1") (pin "12") (pinfunction "NC_12") (pintype "passive+no_connect"))
    )
    (net (code "64") (name "unconnected-(IC1-NC-Pad13)") (class "Default")
      (node (ref "IC1") (pin "13") (pinfunction "NC_13") (pintype "passive+no_connect"))
    )
    (net (code "65") (name "unconnected-(IC1-NC-Pad46)") (class "Default")
      (node (ref "IC1") (pin "46") (pinfunction "NC_46") (pintype "passive+no_connect"))
    )
    (net (code "66") (name "unconnected-(IC1-NC-Pad47)") (class "Default")
      (node (ref "IC1") (pin "47") (pinfunction "NC_47") (pintype "passive+no_connect"))
    )
    (net (code "67") (name "unconnected-(IC1-SPDLED-Pad24)") (class "Default")
      (node (ref "IC1") (pin "24") (pinfunction "SPDLED_24") (pintype "passive+no_connect"))
    )
    (net (code "68") (name "unconnected-(IC1-VBG-Pad18)") (class "Default")
      (node (ref "IC1") (pin "18") (pinfunction "VBG_18") (pintype "passive+no_connect"))
    )
    (net (code "69") (name "unconnected-(IC2-VREF-Pad5)") (class "Default")
      (node (ref "IC2") (pin "5") (pinfunction "VREF_5") (pintype "passive+no_connect"))
    )
    (net (code "70") (name "unconnected-(RJ？1-NC-Pad7)") (class "Default")
      (node (ref "RJ？1") (pin "7") (pinfunction "NC_7") (pintype "passive+no_connect"))
    )
    (net (code "71") (name "unconnected-(U1-I2C2_SCL{slash}PB10-Pad21)") (class "Default")
      (node (ref "U1") (pin "21") (pinfunction "I2C2_SCL/PB10_21") (pintype "bidirectional"))
    )
    (net (code "72") (name "unconnected-(U1-I2C2_SDA{slash}PB11-Pad22)") (class "Default")
      (node (ref "U1") (pin "22") (pinfunction "I2C2_SDA/PB11_22") (pintype "bidirectional"))
    )
    (net (code "73") (name "unconnected-(U1-PA0{slash}WKUP{slash}ADC12_IN0-Pad10)") (class "Default")
      (node (ref "U1") (pin "10") (pinfunction "PA0/WKUP/ADC12_IN0_10") (pintype "bidirectional"))
    )
    (net (code "74") (name "unconnected-(U1-PA1{slash}TIM2_CH2-Pad11)") (class "Default")
      (node (ref "U1") (pin "11") (pinfunction "PA1/TIM2_CH2_11") (pintype "bidirectional"))
    )
    (net (code "75") (name "unconnected-(U1-PA2{slash}USART2_TX-Pad12)") (class "Default")
      (node (ref "U1") (pin "12") (pinfunction "PA2/USART2_TX_12") (pintype "bidirectional"))
    )
    (net (code "76") (name "unconnected-(U1-PA5{slash}ADC12_IN5-Pad15)") (class "Default")
      (node (ref "U1") (pin "15") (pinfunction "PA5/ADC12_IN5_15") (pintype "bidirectional"))
    )
    (net (code "77") (name "unconnected-(U1-PA6{slash}TIM3_CH1-Pad16)") (class "Default")
      (node (ref "U1") (pin "16") (pinfunction "PA6/TIM3_CH1_16") (pintype "bidirectional"))
    )
    (net (code "78") (name "unconnected-(U1-PA7{slash}TIM3_CH2-Pad17)") (class "Default")
      (node (ref "U1") (pin "17") (pinfunction "PA7/TIM3_CH2_17") (pintype "bidirectional"))
    )
    (net (code "79") (name "unconnected-(U1-PA8{slash}TIM1_CH1-Pad29)") (class "Default")
      (node (ref "U1") (pin "29") (pinfunction "PA8/TIM1_CH1_29") (pintype "bidirectional"))
    )
    (net (code "80") (name "unconnected-(U1-PA9{slash}USART1_TX-Pad30)") (class "Default")
      (node (ref "U1") (pin "30") (pinfunction "PA9/USART1_TX_30") (pintype "bidirectional"))
    )
    (net (code "81") (name "unconnected-(U1-PA10{slash}USART1_RX-Pad31)") (class "Default")
      (node (ref "U1") (pin "31") (pinfunction "PA10/USART1_RX_31") (pintype "bidirectional"))
    )
    (net (code "82") (name "unconnected-(U1-PA15{slash}JTDI-Pad38)") (class "Default")
      (node (ref "U1") (pin "38") (pinfunction "PA15/JTDI_38") (pintype "bidirectional"))
    )
    (net (code "83") (name "unconnected-(U1-PB3{slash}JTDO-Pad39)") (class "Default")
      (node (ref "U1") (pin "39") (pinfunction "PB3/JTDO_39") (pintype "bidirectional"))
    )
    (net (code "84") (name "unconnected-(U1-PC13-TAMPER-RTC-Pad2)") (class "Default")
      (node (ref "U1") (pin "2") (pinfunction "PC13-TAMPER-RTC_2") (pintype "bidirectional"))
    )
    (net (code "85") (name "unconnected-(U1-PC14-OSC32_IN-Pad3)") (class "Default")
      (node (ref "U1") (pin "3") (pinfunction "PC14-OSC32_IN_3") (pintype "bidirectional"))
    )
    (net (code "86") (name "unconnected-(U1-PC15-OSC32_OUT-Pad4)") (class "Default")
      (node (ref "U1") (pin "4") (pinfunction "PC15-OSC32_OUT_4") (pintype "bidirectional"))
    )
    (net (code "87") (name "unconnected-(U1-SPI2_NSS{slash}PB12-Pad25)") (class "Default")
      (node (ref "U1") (pin "25") (pinfunction "SPI2_NSS/PB12_25") (pintype "bidirectional"))
    )
    (net (code "88") (name "unconnected-(U1-TIM3_CH3{slash}PB0-Pad18)") (class "Default")
      (node (ref "U1") (pin "18") (pinfunction "TIM3_CH3/PB0_18") (pintype "bidirectional"))
    )
    (net (code "89") (name "unconnected-(U1-TIM3_CH4{slash}PB1-Pad19)") (class "Default")
      (node (ref "U1") (pin "19") (pinfunction "TIM3_CH4/PB1_19") (pintype "bidirectional"))
    )
    (net (code "90") (name "unconnected-(U1-TIM4_CH1{slash}PB6-Pad42)") (class "Default")
      (node (ref "U1") (pin "42") (pinfunction "TIM4_CH1/PB6_42") (pintype "bidirectional"))
    )
    (net (code "91") (name "unconnected-(U1-TIM4_CH2{slash}PB7-Pad43)") (class "Default")
      (node (ref "U1") (pin "43") (pinfunction "TIM4_CH2/PB7_43") (pintype "bidirectional"))
    )
    (net (code "92") (name "unconnected-(U1-TIM4_CH3{slash}PB8-Pad45)") (class "Default")
      (node (ref "U1") (pin "45") (pinfunction "TIM4_CH3/PB8_45") (pintype "bidirectional"))
    )
  )
)
